# Sec_Controller_Sheet2.net
KiCad netlist of a schematic drawn in Altium Designer
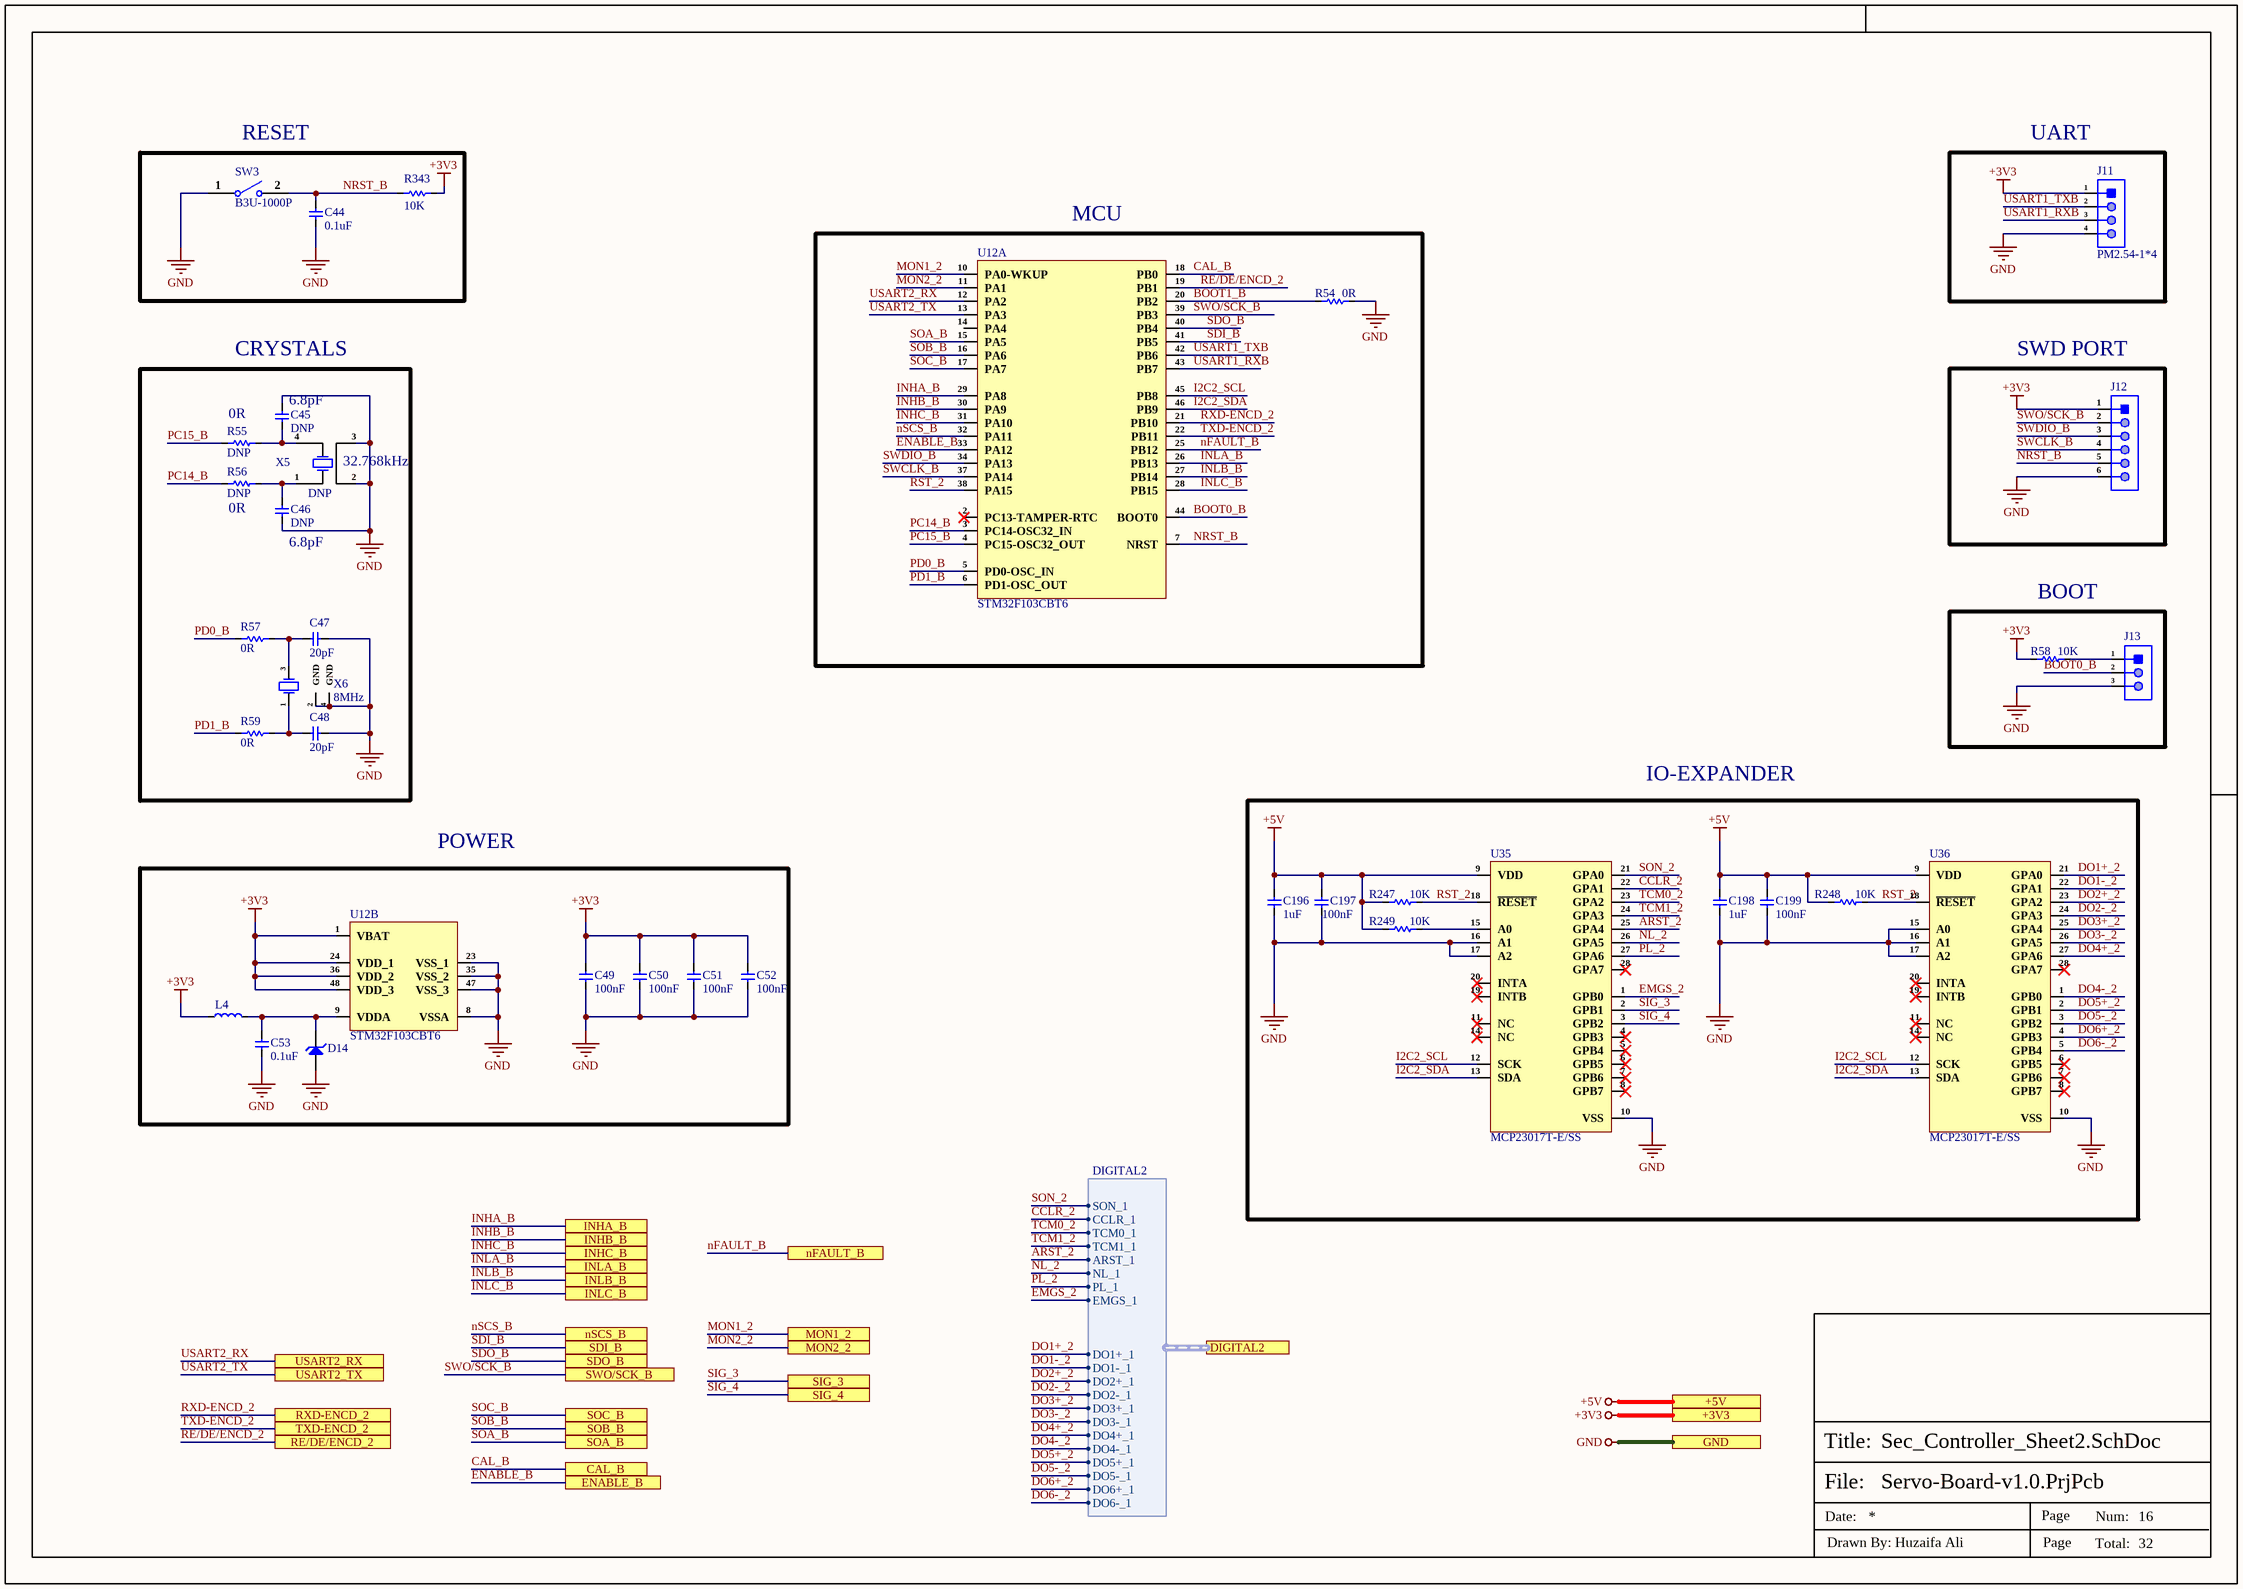
[diagram p0: Sec_Controller_Sheet2.SchDoc]

(export (version "E")
  (design (tool "Eeschema 10.0.6"))
  (components
    (comp (ref "C44")
      (value "0.1uF")
      (footprint "Cap-0402")
      (description "CAP CER 0.1UF 16V X7R 0402")
      (fields
        (field (name "MANUFACTURER") "Yageo")
        (field (name "MANUFACTURER PART NUMBER") "CC0402JRX7R7BB104")
      )
      (libsource (lib "eSpark Libraries") (part "CC0402JRX7R7BB104"))
    )
    (comp (ref "C45")
      (value "DNP")
      (footprint "Cap-0402")
      (description "CAP CER 6.8PF 50V C0G/NPO 0402")
      (fields
        (field (name "MANUFACTURER") "Yageo")
        (field (name "MANUFACTURER PART NUMBER") "CC0402CRNPO9BN6R8")
      )
      (libsource (lib "eSpark Libraries") (part "CC0402CRNPO9BN6R8"))
    )
    (comp (ref "C46")
      (value "DNP")
      (footprint "Cap-0402")
      (description "CAP CER 6.8PF 50V C0G/NPO 0402")
      (fields
        (field (name "MANUFACTURER") "Yageo")
        (field (name "MANUFACTURER PART NUMBER") "CC0402CRNPO9BN6R8")
      )
      (libsource (lib "eSpark Libraries") (part "CC0402CRNPO9BN6R8"))
    )
    (comp (ref "C47")
      (value "20pF")
      (footprint "Cap-0402")
      (description "CAP CER 20PF 50V C0G/NPO 0402")
      (fields (field (name "LCSC PART NUMBER") "C107000") (field (name "MANUFACTURER") "Yageo"))
      (libsource (lib "eSpark Libraries") (part "CC0402JRNPO9BN200"))
    )
    (comp (ref "C48")
      (value "20pF")
      (footprint "Cap-0402")
      (description "CAP CER 20PF 50V C0G/NPO 0402")
      (fields (field (name "LCSC PART NUMBER") "C107000") (field (name "MANUFACTURER") "Yageo"))
      (libsource (lib "eSpark Libraries") (part "CC0402JRNPO9BN200"))
    )
    (comp (ref "C49")
      (value "100nF")
      (footprint "cap-0402")
      (description "CAP CER 0.1UF 50V X7R 0402")
      (fields
        (field (name "MANUFACTURER") "TDK")
        (field (name "MANUFACTURER PART NUMBER") "C1005X7R1H104KT000F")
      )
      (libsource (lib "eSpark Libraries") (part "C1005X7R1H104KT000F"))
    )
    (comp (ref "C50")
      (value "100nF")
      (footprint "cap-0402")
      (description "CAP CER 0.1UF 50V X7R 0402")
      (fields
        (field (name "MANUFACTURER") "TDK")
        (field (name "MANUFACTURER PART NUMBER") "C1005X7R1H104KT000F")
      )
      (libsource (lib "eSpark Libraries") (part "C1005X7R1H104KT000F"))
    )
    (comp (ref "C51")
      (value "100nF")
      (footprint "cap-0402")
      (description "CAP CER 0.1UF 50V X7R 0402")
      (fields
        (field (name "MANUFACTURER") "TDK")
        (field (name "MANUFACTURER PART NUMBER") "C1005X7R1H104KT000F")
      )
      (libsource (lib "eSpark Libraries") (part "C1005X7R1H104KT000F"))
    )
    (comp (ref "C52")
      (value "100nF")
      (footprint "cap-0402")
      (description "CAP CER 0.1UF 50V X7R 0402")
      (fields
        (field (name "MANUFACTURER") "TDK")
        (field (name "MANUFACTURER PART NUMBER") "C1005X7R1H104KT000F")
      )
      (libsource (lib "eSpark Libraries") (part "C1005X7R1H104KT000F"))
    )
    (comp (ref "C53")
      (value "0.1uF")
      (footprint "Cap-0402")
      (description "CAP CER 0.1UF 16V X7R 0402")
      (fields
        (field (name "MANUFACTURER") "Yageo")
        (field (name "MANUFACTURER PART NUMBER") "CC0402JRX7R7BB104")
      )
      (libsource (lib "eSpark Libraries") (part "CC0402JRX7R7BB104"))
    )
    (comp (ref "C196")
      (value "1uF")
      (footprint "Cap-0402")
      (description "CAP CER 1UF 10V X5R 0402")
      (fields
        (field (name "MANUFACTURER") "Yageo")
        (field (name "MANUFACTURER PART NUMBER") "CC0402KRX5R6BB105")
      )
      (libsource (lib "eSpark Libraries") (part "CC0402KRX5R6BB105"))
    )
    (comp (ref "C197")
      (value "100nF")
      (footprint "cap-0402")
      (description "CAP CER 0.1UF 50V X7R 0402")
      (fields
        (field (name "MANUFACTURER") "TDK")
        (field (name "MANUFACTURER PART NUMBER") "C1005X7R1H104KT000F")
      )
      (libsource (lib "eSpark Libraries") (part "C1005X7R1H104KT000F"))
    )
    (comp (ref "C198")
      (value "1uF")
      (footprint "Cap-0402")
      (description "CAP CER 1UF 10V X5R 0402")
      (fields
        (field (name "MANUFACTURER") "Yageo")
        (field (name "MANUFACTURER PART NUMBER") "CC0402KRX5R6BB105")
      )
      (libsource (lib "eSpark Libraries") (part "CC0402KRX5R6BB105"))
    )
    (comp (ref "C199")
      (value "100nF")
      (footprint "cap-0402")
      (description "CAP CER 0.1UF 50V X7R 0402")
      (fields
        (field (name "MANUFACTURER") "TDK")
        (field (name "MANUFACTURER PART NUMBER") "C1005X7R1H104KT000F")
      )
      (libsource (lib "eSpark Libraries") (part "C1005X7R1H104KT000F"))
    )
    (comp (ref "D14")
      (value "AZ3003-01G")
      (footprint "SOD-123")
      (description "TVS SURGE PROTECTOR 1-CH 3.3V")
      (fields (field (name "MANUFACTURER") "Amazing"))
      (libsource (lib "eSpark Libraries") (part "AZ3003-01G"))
    )
    (comp (ref "J11")
      (value "PM2.54-1*4")
      (footprint "HDR1X4 Female")
      (fields (field (name "MANUFACTURER") "ZHOURI") (field (name "LCSC PART NUMBER") "C5116530"))
      (libsource (lib "eSpark Libraries") (part "PM2.54-1*4"))
    )
    (comp (ref "J12")
      (value "X6511WV-06H-C60D30")
      (footprint "HDR1X6_")
      (fields (field (name "MANUFACTURER") "XKB") (field (name "LCSC PART NUMBER") "C706878"))
      (libsource (lib "eSpark Libraries") (part "X6511WV-06H-C60D30"))
    )
    (comp (ref "J13")
      (value "68000-103HLF")
      (footprint "HDR1X3_")
      (description "CONN HEADER VERT 3POS 2.54MM")
      (fields (field (name "LCSC PART NUMBER") "C168677"))
      (libsource (lib "eSpark Libraries") (part "68000-103HLF"))
    )
    (comp (ref "L4")
      (value "BLM15AG601SN1D")
      (footprint "IND-0402")
      (description "FERRITE BEAD 600 OHM 0402 1LN")
      (fields (field (name "MANUFACTURER") "Murata") (field (name "TOLERANCE") "25%"))
      (libsource (lib "eSpark Libraries") (part "BLM15AG601SN1D"))
    )
    (comp (ref "R54")
      (value "0R")
      (footprint "Res-0402")
      (description "RES 0 OHM JUMPER 1/16W 0402")
      (fields
        (field (name "MANUFACTURER") "Yageo")
        (field (name "MANUFACTURER PART NUMBER") "RC0402FR-070RL")
      )
      (libsource (lib "eSpark Libraries") (part "RC0402FR-070RL"))
    )
    (comp (ref "R55")
      (value "DNP")
      (footprint "Res-0603")
      (description "RES 0 OHM JUMPER 1/10W 0603")
      (fields
        (field (name "MANUFACTURER") "Yageo")
        (field (name "MANUFACTURER PART NUMBER") "RC0603JR-070RL")
      )
      (libsource (lib "eSpark Libraries") (part "RC0603JR-070RL"))
    )
    (comp (ref "R56")
      (value "DNP")
      (footprint "Res-0603")
      (description "RES 0 OHM JUMPER 1/10W 0603")
      (fields
        (field (name "MANUFACTURER") "Yageo")
        (field (name "MANUFACTURER PART NUMBER") "RC0603JR-070RL")
      )
      (libsource (lib "eSpark Libraries") (part "RC0603JR-070RL"))
    )
    (comp (ref "R57")
      (value "0R")
      (footprint "Res-0603")
      (description "RES 0 OHM JUMPER 1/10W 0603")
      (fields
        (field (name "MANUFACTURER") "Yageo")
        (field (name "MANUFACTURER PART NUMBER") "RC0603JR-070RL")
      )
      (libsource (lib "eSpark Libraries") (part "RC0603JR-070RL"))
    )
    (comp (ref "R58")
      (value "10K")
      (footprint "Res-0402")
      (description "RES 10K OHM 1% 1/16W 0402")
      (fields
        (field (name "MANUFACTURER") "Yageo")
        (field (name "MANUFACTURER PART NUMBER") "RC0402FR-0710KL")
      )
      (libsource (lib "eSpark Libraries") (part "RC0402FR-0710KL"))
    )
    (comp (ref "R59")
      (value "0R")
      (footprint "Res-0603")
      (description "RES 0 OHM JUMPER 1/10W 0603")
      (fields
        (field (name "MANUFACTURER") "Yageo")
        (field (name "MANUFACTURER PART NUMBER") "RC0603JR-070RL")
      )
      (libsource (lib "eSpark Libraries") (part "RC0603JR-070RL"))
    )
    (comp (ref "R247")
      (value "10K")
      (footprint "Res-0402")
      (description "RES 10K OHM 1% 1/16W 0402")
      (fields
        (field (name "MANUFACTURER") "Yageo")
        (field (name "MANUFACTURER PART NUMBER") "RC0402FR-0710KL")
      )
      (libsource (lib "eSpark Libraries") (part "RC0402FR-0710KL"))
    )
    (comp (ref "R248")
      (value "10K")
      (footprint "Res-0402")
      (description "RES 10K OHM 1% 1/16W 0402")
      (fields
        (field (name "MANUFACTURER") "Yageo")
        (field (name "MANUFACTURER PART NUMBER") "RC0402FR-0710KL")
      )
      (libsource (lib "eSpark Libraries") (part "RC0402FR-0710KL"))
    )
    (comp (ref "R249")
      (value "10K")
      (footprint "Res-0402")
      (description "RES 10K OHM 1% 1/16W 0402")
      (fields
        (field (name "MANUFACTURER") "Yageo")
        (field (name "MANUFACTURER PART NUMBER") "RC0402FR-0710KL")
      )
      (libsource (lib "eSpark Libraries") (part "RC0402FR-0710KL"))
    )
    (comp (ref "R343")
      (value "10K")
      (footprint "Res-0402")
      (description "RES 10K OHM 1% 1/16W 0402")
      (fields
        (field (name "MANUFACTURER") "Yageo")
        (field (name "MANUFACTURER PART NUMBER") "RC0402FR-0710KL")
      )
      (libsource (lib "eSpark Libraries") (part "RC0402FR-0710KL"))
    )
    (comp (ref "SW3")
      (value "B3U-1000P")
      (footprint "B3U-1000P")
      (description "SWITCH TACTILE SPST-NO 0.05A 12V")
      (fields (field (name "MANUFACTURER") "Omron") (field (name "LCSC PART NUMBER") "C231329"))
      (libsource (lib "eSpark Libraries") (part "B3U-1000P"))
    )
    (comp (ref "U12")
      (value "STM32F103CBT6")
      (footprint "48-LQFP (7x7)_")
      (description "IC MCU 32BIT 128KB FLASH 48LQFP")
      (fields (field (name "MANUFACTURER") "STMicroelectronics") (field (name "LCSC PART NUMBER") "C8304"))
      (libsource (lib "eSpark Libraries") (part "STM32F103CBT6"))
    )
    (comp (ref "U35")
      (value "MCP23017T-E/SS")
      (footprint "SSOP-28-208mil")
      (description "IC XPNDR 1.7MHZ I2C 28SSOP")
      (fields (field (name "MANUFACTURER") "Microchip") (field (name "LCSC PART NUMBER") "C558584"))
      (libsource (lib "eSpark Libraries") (part "MCP23017T-E/SS"))
    )
    (comp (ref "U36")
      (value "MCP23017T-E/SS")
      (footprint "SSOP-28-208mil")
      (description "IC XPNDR 1.7MHZ I2C 28SSOP")
      (fields (field (name "MANUFACTURER") "Microchip") (field (name "LCSC PART NUMBER") "C558584"))
      (libsource (lib "eSpark Libraries") (part "MCP23017T-E/SS"))
    )
    (comp (ref "X5")
      (value "DNP")
      (footprint "MC-306")
      (description "32.768kHz 12.5pF ±20ppm MC-306 Crystals ROHS")
      (fields
        (field (name "MANUFACTURER") "Seiko Epson")
        (field (name "MANUFACTURER PART NUMBER") "MC-306 32.7680K-A0:ROHS")
      )
      (libsource (lib "eSpark Libraries") (part "MC-306 32.7680K-A0{colon}ROHS"))
    )
    (comp (ref "X6")
      (value "8MHz")
      (footprint "5TJ480000XYLBC_")
      (description "8MHz 18pF ±10ppm SMD5032-4P Crystals ROHS")
      (fields (field (name "MANUFACTURER") "JYJE") (field (name "MANUFACTURER PART NUMBER") "5TJ480000XYLBC"))
      (libsource (lib "eSpark Libraries") (part "5TJ480000XYLBC"))
    )
  )
  (nets
    (net (code "2") (name "+3V3") (class "Default")
      (node (ref "C49") (pin "2") (pinfunction "2_2") (pintype "passive"))
      (node (ref "C50") (pin "2") (pinfunction "2_2") (pintype "passive"))
      (node (ref "C51") (pin "2") (pinfunction "2_2") (pintype "passive"))
      (node (ref "C52") (pin "2") (pinfunction "2_2") (pintype "passive"))
      (node (ref "J11") (pin "1") (pinfunction "1_1") (pintype "passive"))
      (node (ref "J12") (pin "1") (pinfunction "1_1") (pintype "passive"))
      (node (ref "L4") (pin "1") (pinfunction "1_1") (pintype "passive"))
      (node (ref "R343") (pin "2") (pinfunction "2_2") (pintype "passive"))
      (node (ref "R58") (pin "2") (pinfunction "2_2") (pintype "passive"))
      (node (ref "U12") (pin "1") (pinfunction "VBAT_1") (pintype "power_in"))
      (node (ref "U12") (pin "24") (pinfunction "VDD_1_24") (pintype "power_in"))
      (node (ref "U12") (pin "36") (pinfunction "VDD_2_36") (pintype "power_in"))
      (node (ref "U12") (pin "48") (pinfunction "VDD_3_48") (pintype "power_in"))
    )
    (net (code "3") (name "+5V") (class "Default")
      (node (ref "C196") (pin "2") (pinfunction "2_2") (pintype "passive"))
      (node (ref "C197") (pin "2") (pinfunction "2_2") (pintype "passive"))
      (node (ref "C198") (pin "2") (pinfunction "2_2") (pintype "passive"))
      (node (ref "C199") (pin "2") (pinfunction "2_2") (pintype "passive"))
      (node (ref "R247") (pin "2") (pinfunction "2_2") (pintype "passive"))
      (node (ref "R248") (pin "2") (pinfunction "2_2") (pintype "passive"))
      (node (ref "R249") (pin "2") (pinfunction "2_2") (pintype "passive"))
      (node (ref "U35") (pin "9") (pinfunction "VDD_9") (pintype "passive"))
      (node (ref "U36") (pin "9") (pinfunction "VDD_9") (pintype "passive"))
    )
    (net (code "4") (name "/ARST_2") (class "Default")
      (node (ref "U35") (pin "25") (pinfunction "GPA4_25") (pintype "passive"))
    )
    (net (code "5") (name "/BOOT0_B") (class "Default")
      (node (ref "J13") (pin "2") (pinfunction "2_2") (pintype "passive"))
      (node (ref "U12") (pin "44") (pinfunction "BOOT0_44") (pintype "passive"))
    )
    (net (code "6") (name "/BOOT1_B") (class "Default")
      (node (ref "R54") (pin "1") (pinfunction "1_1") (pintype "passive"))
      (node (ref "U12") (pin "20") (pinfunction "PB2_20") (pintype "passive"))
    )
    (net (code "7") (name "/CAL_B") (class "Default")
      (node (ref "U12") (pin "18") (pinfunction "PB0_18") (pintype "passive"))
    )
    (net (code "8") (name "/CCLR_2") (class "Default")
      (node (ref "U35") (pin "22") (pinfunction "GPA1_22") (pintype "passive"))
    )
    (net (code "9") (name "/DO1+_2") (class "Default")
      (node (ref "U36") (pin "21") (pinfunction "GPA0_21") (pintype "passive"))
    )
    (net (code "10") (name "/DO1-_2") (class "Default")
      (node (ref "U36") (pin "22") (pinfunction "GPA1_22") (pintype "passive"))
    )
    (net (code "11") (name "/DO2+_2") (class "Default")
      (node (ref "U36") (pin "23") (pinfunction "GPA2_23") (pintype "passive"))
    )
    (net (code "12") (name "/DO2-_2") (class "Default")
      (node (ref "U36") (pin "24") (pinfunction "GPA3_24") (pintype "passive"))
    )
    (net (code "13") (name "/DO3+_2") (class "Default")
      (node (ref "U36") (pin "25") (pinfunction "GPA4_25") (pintype "passive"))
    )
    (net (code "14") (name "/DO3-_2") (class "Default")
      (node (ref "U36") (pin "26") (pinfunction "GPA5_26") (pintype "passive"))
    )
    (net (code "15") (name "/DO4+_2") (class "Default")
      (node (ref "U36") (pin "27") (pinfunction "GPA6_27") (pintype "passive"))
    )
    (net (code "16") (name "/DO4-_2") (class "Default")
      (node (ref "U36") (pin "1") (pinfunction "GPB0_1") (pintype "passive"))
    )
    (net (code "17") (name "/DO5+_2") (class "Default")
      (node (ref "U36") (pin "2") (pinfunction "GPB1_2") (pintype "passive"))
    )
    (net (code "18") (name "/DO5-_2") (class "Default")
      (node (ref "U36") (pin "3") (pinfunction "GPB2_3") (pintype "passive"))
    )
    (net (code "19") (name "/DO6+_2") (class "Default")
      (node (ref "U36") (pin "4") (pinfunction "GPB3_4") (pintype "passive"))
    )
    (net (code "20") (name "/DO6-_2") (class "Default")
      (node (ref "U36") (pin "5") (pinfunction "GPB4_5") (pintype "passive"))
    )
    (net (code "21") (name "/EMGS_2") (class "Default")
      (node (ref "U35") (pin "1") (pinfunction "GPB0_1") (pintype "passive"))
    )
    (net (code "22") (name "/ENABLE_B") (class "Default")
      (node (ref "U12") (pin "33") (pinfunction "PA12_33") (pintype "passive"))
    )
    (net (code "23") (name "/I2C2_SCL") (class "Default")
      (node (ref "U12") (pin "45") (pinfunction "PB8_45") (pintype "passive"))
      (node (ref "U35") (pin "12") (pinfunction "SCK_12") (pintype "passive"))
      (node (ref "U36") (pin "12") (pinfunction "SCK_12") (pintype "passive"))
    )
    (net (code "24") (name "/I2C2_SDA") (class "Default")
      (node (ref "U12") (pin "46") (pinfunction "PB9_46") (pintype "passive"))
      (node (ref "U35") (pin "13") (pinfunction "SDA_13") (pintype "passive"))
      (node (ref "U36") (pin "13") (pinfunction "SDA_13") (pintype "passive"))
    )
    (net (code "25") (name "/INHA_B") (class "Default")
      (node (ref "U12") (pin "29") (pinfunction "PA8_29") (pintype "passive"))
    )
    (net (code "26") (name "/INHB_B") (class "Default")
      (node (ref "U12") (pin "30") (pinfunction "PA9_30") (pintype "passive"))
    )
    (net (code "27") (name "/INHC_B") (class "Default")
      (node (ref "U12") (pin "31") (pinfunction "PA10_31") (pintype "passive"))
    )
    (net (code "28") (name "/INLA_B") (class "Default")
      (node (ref "U12") (pin "26") (pinfunction "PB13_26") (pintype "passive"))
    )
    (net (code "29") (name "/INLB_B") (class "Default")
      (node (ref "U12") (pin "27") (pinfunction "PB14_27") (pintype "passive"))
    )
    (net (code "30") (name "/INLC_B") (class "Default")
      (node (ref "U12") (pin "28") (pinfunction "PB15_28") (pintype "passive"))
    )
    (net (code "31") (name "/MON1_2") (class "Default")
      (node (ref "U12") (pin "10") (pinfunction "PA0-WKUP_10") (pintype "passive"))
    )
    (net (code "32") (name "/MON2_2") (class "Default")
      (node (ref "U12") (pin "11") (pinfunction "PA1_11") (pintype "passive"))
    )
    (net (code "33") (name "/NL_2") (class "Default")
      (node (ref "U35") (pin "26") (pinfunction "GPA5_26") (pintype "passive"))
    )
    (net (code "34") (name "/NRST_B") (class "Default")
      (node (ref "C44") (pin "2") (pinfunction "2_2") (pintype "passive"))
      (node (ref "J12") (pin "5") (pinfunction "5_5") (pintype "passive"))
      (node (ref "R343") (pin "1") (pinfunction "1_1") (pintype "passive"))
      (node (ref "SW3") (pin "2") (pinfunction "2_2") (pintype "passive"))
      (node (ref "U12") (pin "7") (pinfunction "NRST_7") (pintype "passive"))
    )
    (net (code "35") (name "/PC14_B") (class "Default")
      (node (ref "R56") (pin "2") (pinfunction "2_2") (pintype "passive"))
      (node (ref "U12") (pin "3") (pinfunction "PC14-OSC32_IN_3") (pintype "passive"))
    )
    (net (code "36") (name "/PC15_B") (class "Default")
      (node (ref "R55") (pin "2") (pinfunction "2_2") (pintype "passive"))
      (node (ref "U12") (pin "4") (pinfunction "PC15-OSC32_OUT_4") (pintype "passive"))
    )
    (net (code "37") (name "/PD0_B") (class "Default")
      (node (ref "R57") (pin "2") (pinfunction "2_2") (pintype "passive"))
      (node (ref "U12") (pin "5") (pinfunction "PD0-OSC_IN_5") (pintype "passive"))
    )
    (net (code "38") (name "/PD1_B") (class "Default")
      (node (ref "R59") (pin "2") (pinfunction "2_2") (pintype "passive"))
      (node (ref "U12") (pin "6") (pinfunction "PD1-OSC_OUT_6") (pintype "passive"))
    )
    (net (code "39") (name "/PL_2") (class "Default")
      (node (ref "U35") (pin "27") (pinfunction "GPA6_27") (pintype "passive"))
    )
    (net (code "40") (name "/RE{slash}DE{slash}ENCD_2") (class "Default")
      (node (ref "U12") (pin "19") (pinfunction "PB1_19") (pintype "passive"))
    )
    (net (code "41") (name "/RST_2") (class "Default")
      (node (ref "R247") (pin "1") (pinfunction "1_1") (pintype "passive"))
      (node (ref "R248") (pin "1") (pinfunction "1_1") (pintype "passive"))
      (node (ref "U12") (pin "38") (pinfunction "PA15_38") (pintype "passive"))
      (node (ref "U35") (pin "18") (pinfunction "~{RESET}_18") (pintype "passive"))
      (node (ref "U36") (pin "18") (pinfunction "~{RESET}_18") (pintype "passive"))
    )
    (net (code "42") (name "/RXD-ENCD_2") (class "Default")
      (node (ref "U12") (pin "21") (pinfunction "PB10_21") (pintype "passive"))
    )
    (net (code "43") (name "/SDI_B") (class "Default")
      (node (ref "U12") (pin "41") (pinfunction "PB5_41") (pintype "passive"))
    )
    (net (code "44") (name "/SDO_B") (class "Default")
      (node (ref "U12") (pin "40") (pinfunction "PB4_40") (pintype "passive"))
    )
    (net (code "45") (name "/SIG_3") (class "Default")
      (node (ref "U35") (pin "2") (pinfunction "GPB1_2") (pintype "passive"))
    )
    (net (code "46") (name "/SIG_4") (class "Default")
      (node (ref "U35") (pin "3") (pinfunction "GPB2_3") (pintype "passive"))
    )
    (net (code "47") (name "/SOA_B") (class "Default")
      (node (ref "U12") (pin "15") (pinfunction "PA5_15") (pintype "passive"))
    )
    (net (code "48") (name "/SOB_B") (class "Default")
      (node (ref "U12") (pin "16") (pinfunction "PA6_16") (pintype "passive"))
    )
    (net (code "49") (name "/SOC_B") (class "Default")
      (node (ref "U12") (pin "17") (pinfunction "PA7_17") (pintype "passive"))
    )
    (net (code "50") (name "/SON_2") (class "Default")
      (node (ref "U35") (pin "21") (pinfunction "GPA0_21") (pintype "passive"))
    )
    (net (code "51") (name "/SWCLK_B") (class "Default")
      (node (ref "J12") (pin "4") (pinfunction "4_4") (pintype "passive"))
      (node (ref "U12") (pin "37") (pinfunction "PA14_37") (pintype "passive"))
    )
    (net (code "52") (name "/SWDIO_B") (class "Default")
      (node (ref "J12") (pin "3") (pinfunction "3_3") (pintype "passive"))
      (node (ref "U12") (pin "34") (pinfunction "PA13_34") (pintype "passive"))
    )
    (net (code "53") (name "/SWO{slash}SCK_B") (class "Default")
      (node (ref "J12") (pin "2") (pinfunction "2_2") (pintype "passive"))
      (node (ref "U12") (pin "39") (pinfunction "PB3_39") (pintype "passive"))
    )
    (net (code "54") (name "/TCM0_2") (class "Default")
      (node (ref "U35") (pin "23") (pinfunction "GPA2_23") (pintype "passive"))
    )
    (net (code "55") (name "/TCM1_2") (class "Default")
      (node (ref "U35") (pin "24") (pinfunction "GPA3_24") (pintype "passive"))
    )
    (net (code "56") (name "/TXD-ENCD_2") (class "Default")
      (node (ref "U12") (pin "22") (pinfunction "PB11_22") (pintype "passive"))
    )
    (net (code "57") (name "/USART1_RXB") (class "Default")
      (node (ref "J11") (pin "3") (pinfunction "3_3") (pintype "passive"))
      (node (ref "U12") (pin "43") (pinfunction "PB7_43") (pintype "passive"))
    )
    (net (code "58") (name "/USART1_TXB") (class "Default")
      (node (ref "J11") (pin "2") (pinfunction "2_2") (pintype "passive"))
      (node (ref "U12") (pin "42") (pinfunction "PB6_42") (pintype "passive"))
    )
    (net (code "59") (name "/USART2_RX") (class "Default")
      (node (ref "U12") (pin "12") (pinfunction "PA2_12") (pintype "passive"))
    )
    (net (code "60") (name "/USART2_TX") (class "Default")
      (node (ref "U12") (pin "13") (pinfunction "PA3_13") (pintype "passive"))
    )
    (net (code "61") (name "/nFAULT_B") (class "Default")
      (node (ref "U12") (pin "25") (pinfunction "PB12_25") (pintype "passive"))
    )
    (net (code "62") (name "/nSCS_B") (class "Default")
      (node (ref "U12") (pin "32") (pinfunction "PA11_32") (pintype "passive"))
    )
    (net (code "64") (name "GND") (class "Default")
      (node (ref "C196") (pin "1") (pinfunction "1_1") (pintype "passive"))
      (node (ref "C197") (pin "1") (pinfunction "1_1") (pintype "passive"))
      (node (ref "C198") (pin "1") (pinfunction "1_1") (pintype "passive"))
      (node (ref "C199") (pin "1") (pinfunction "1_1") (pintype "passive"))
      (node (ref "C44") (pin "1") (pinfunction "1_1") (pintype "passive"))
      (node (ref "C45") (pin "2") (pinfunction "2_2") (pintype "passive"))
      (node (ref "C46") (pin "1") (pinfunction "1_1") (pintype "passive"))
      (node (ref "C47") (pin "2") (pinfunction "2_2") (pintype "passive"))
      (node (ref "C48") (pin "2") (pinfunction "2_2") (pintype "passive"))
      (node (ref "C49") (pin "1") (pinfunction "1_1") (pintype "passive"))
      (node (ref "C50") (pin "1") (pinfunction "1_1") (pintype "passive"))
      (node (ref "C51") (pin "1") (pinfunction "1_1") (pintype "passive"))
      (node (ref "C52") (pin "1") (pinfunction "1_1") (pintype "passive"))
      (node (ref "C53") (pin "1") (pinfunction "1_1") (pintype "passive"))
      (node (ref "D14") (pin "1") (pinfunction "A_1") (pintype "passive"))
      (node (ref "J11") (pin "4") (pinfunction "4_4") (pintype "passive"))
      (node (ref "J12") (pin "6") (pinfunction "6_6") (pintype "passive"))
      (node (ref "J13") (pin "3") (pinfunction "3_3") (pintype "passive"))
      (node (ref "R54") (pin "2") (pinfunction "2_2") (pintype "passive"))
      (node (ref "SW3") (pin "1") (pinfunction "1_1") (pintype "passive"))
      (node (ref "U12") (pin "23") (pinfunction "VSS_1_23") (pintype "power_in"))
      (node (ref "U12") (pin "35") (pinfunction "VSS_2_35") (pintype "power_in"))
      (node (ref "U12") (pin "47") (pinfunction "VSS_3_47") (pintype "power_in"))
      (node (ref "U12") (pin "8") (pinfunction "VSSA_8") (pintype "power_in"))
      (node (ref "U35") (pin "10") (pinfunction "VSS_10") (pintype "passive"))
      (node (ref "U35") (pin "16") (pinfunction "A1_16") (pintype "passive"))
      (node (ref "U35") (pin "17") (pinfunction "A2_17") (pintype "passive"))
      (node (ref "U36") (pin "10") (pinfunction "VSS_10") (pintype "passive"))
      (node (ref "U36") (pin "15") (pinfunction "A0_15") (pintype "passive"))
      (node (ref "U36") (pin "16") (pinfunction "A1_16") (pintype "passive"))
      (node (ref "U36") (pin "17") (pinfunction "A2_17") (pintype "passive"))
      (node (ref "X5") (pin "2") (pinfunction "2_2") (pintype "passive"))
      (node (ref "X5") (pin "3") (pinfunction "3_3") (pintype "passive"))
      (node (ref "X6") (pin "2") (pinfunction "GND_2") (pintype "passive"))
      (node (ref "X6") (pin "4") (pinfunction "GND_4") (pintype "passive"))
    )
    (net (code "65") (name "Net-(D14-K)") (class "Default")
      (node (ref "C53") (pin "2") (pinfunction "2_2") (pintype "passive"))
      (node (ref "D14") (pin "2") (pinfunction "K_2") (pintype "passive"))
      (node (ref "L4") (pin "2") (pinfunction "2_2") (pintype "passive"))
      (node (ref "U12") (pin "9") (pinfunction "VDDA_9") (pintype "power_in"))
    )
    (net (code "66") (name "Net-(J13-Pad1)") (class "Default")
      (node (ref "J13") (pin "1") (pinfunction "1_1") (pintype "passive"))
      (node (ref "R58") (pin "1") (pinfunction "1_1") (pintype "passive"))
    )
    (net (code "67") (name "Net-(U35-A0)") (class "Default")
      (node (ref "R249") (pin "1") (pinfunction "1_1") (pintype "passive"))
      (node (ref "U35") (pin "15") (pinfunction "A0_15") (pintype "passive"))
    )
    (net (code "68") (name "Net-(X5-OSC1)") (class "Default")
      (node (ref "C46") (pin "2") (pinfunction "2_2") (pintype "passive"))
      (node (ref "R56") (pin "1") (pinfunction "1_1") (pintype "passive"))
      (node (ref "X5") (pin "1") (pinfunction "OSC1_1") (pintype "passive"))
    )
    (net (code "69") (name "Net-(X5-OSC2)") (class "Default")
      (node (ref "C45") (pin "1") (pinfunction "1_1") (pintype "passive"))
      (node (ref "R55") (pin "1") (pinfunction "1_1") (pintype "passive"))
      (node (ref "X5") (pin "4") (pinfunction "OSC2_4") (pintype "passive"))
    )
    (net (code "70") (name "Net-(X6-OSC1)") (class "Default")
      (node (ref "C48") (pin "1") (pinfunction "1_1") (pintype "passive"))
      (node (ref "R59") (pin "1") (pinfunction "1_1") (pintype "passive"))
      (node (ref "X6") (pin "1") (pinfunction "OSC1_1") (pintype "passive"))
    )
    (net (code "71") (name "Net-(X6-OSC2)") (class "Default")
      (node (ref "C47") (pin "1") (pinfunction "1_1") (pintype "passive"))
      (node (ref "R57") (pin "1") (pinfunction "1_1") (pintype "passive"))
      (node (ref "X6") (pin "3") (pinfunction "OSC2_3") (pintype "passive"))
    )
    (net (code "72") (name "unconnected-(U12A-PA4-Pad14)") (class "Default")
      (node (ref "U12") (pin "14") (pinfunction "PA4_14") (pintype "passive"))
    )
    (net (code "73") (name "unconnected-(U12A-PC13-TAMPER-RTC-Pad2)") (class "Default")
      (node (ref "U12") (pin "2") (pinfunction "PC13-TAMPER-RTC_2") (pintype "passive+no_connect"))
    )
    (net (code "74") (name "unconnected-(U35-GPA7-Pad28)") (class "Default")
      (node (ref "U35") (pin "28") (pinfunction "GPA7_28") (pintype "passive+no_connect"))
    )
    (net (code "75") (name "unconnected-(U35-GPB3-Pad4)") (class "Default")
      (node (ref "U35") (pin "4") (pinfunction "GPB3_4") (pintype "passive+no_connect"))
    )
    (net (code "76") (name "unconnected-(U35-GPB4-Pad5)") (class "Default")
      (node (ref "U35") (pin "5") (pinfunction "GPB4_5") (pintype "passive+no_connect"))
    )
    (net (code "77") (name "unconnected-(U35-GPB5-Pad6)") (class "Default")
      (node (ref "U35") (pin "6") (pinfunction "GPB5_6") (pintype "passive+no_connect"))
    )
    (net (code "78") (name "unconnected-(U35-GPB6-Pad7)") (class "Default")
      (node (ref "U35") (pin "7") (pinfunction "GPB6_7") (pintype "passive+no_connect"))
    )
    (net (code "79") (name "unconnected-(U35-GPB7-Pad8)") (class "Default")
      (node (ref "U35") (pin "8") (pinfunction "GPB7_8") (pintype "passive+no_connect"))
    )
    (net (code "80") (name "unconnected-(U35-INTA-Pad20)") (class "Default")
      (node (ref "U35") (pin "20") (pinfunction "INTA_20") (pintype "passive+no_connect"))
    )
    (net (code "81") (name "unconnected-(U35-INTB-Pad19)") (class "Default")
      (node (ref "U35") (pin "19") (pinfunction "INTB_19") (pintype "passive+no_connect"))
    )
    (net (code "82") (name "unconnected-(U35-NC-Pad11)") (class "Default")
      (node (ref "U35") (pin "11") (pinfunction "NC_11") (pintype "passive+no_connect"))
    )
    (net (code "83") (name "unconnected-(U35-NC-Pad14)") (class "Default")
      (node (ref "U35") (pin "14") (pinfunction "NC_14") (pintype "passive+no_connect"))
    )
    (net (code "84") (name "unconnected-(U36-GPA7-Pad28)") (class "Default")
      (node (ref "U36") (pin "28") (pinfunction "GPA7_28") (pintype "passive+no_connect"))
    )
    (net (code "85") (name "unconnected-(U36-GPB5-Pad6)") (class "Default")
      (node (ref "U36") (pin "6") (pinfunction "GPB5_6") (pintype "passive+no_connect"))
    )
    (net (code "86") (name "unconnected-(U36-GPB6-Pad7)") (class "Default")
      (node (ref "U36") (pin "7") (pinfunction "GPB6_7") (pintype "passive+no_connect"))
    )
    (net (code "87") (name "unconnected-(U36-GPB7-Pad8)") (class "Default")
      (node (ref "U36") (pin "8") (pinfunction "GPB7_8") (pintype "passive+no_connect"))
    )
    (net (code "88") (name "unconnected-(U36-INTA-Pad20)") (class "Default")
      (node (ref "U36") (pin "20") (pinfunction "INTA_20") (pintype "passive+no_connect"))
    )
    (net (code "89") (name "unconnected-(U36-INTB-Pad19)") (class "Default")
      (node (ref "U36") (pin "19") (pinfunction "INTB_19") (pintype "passive+no_connect"))
    )
    (net (code "90") (name "unconnected-(U36-NC-Pad11)") (class "Default")
      (node (ref "U36") (pin "11") (pinfunction "NC_11") (pintype "passive+no_connect"))
    )
    (net (code "91") (name "unconnected-(U36-NC-Pad14)") (class "Default")
      (node (ref "U36") (pin "14") (pinfunction "NC_14") (pintype "passive+no_connect"))
    )
  )
)
